# TOP.net
KiCad netlist of a schematic drawn in Altium Designer
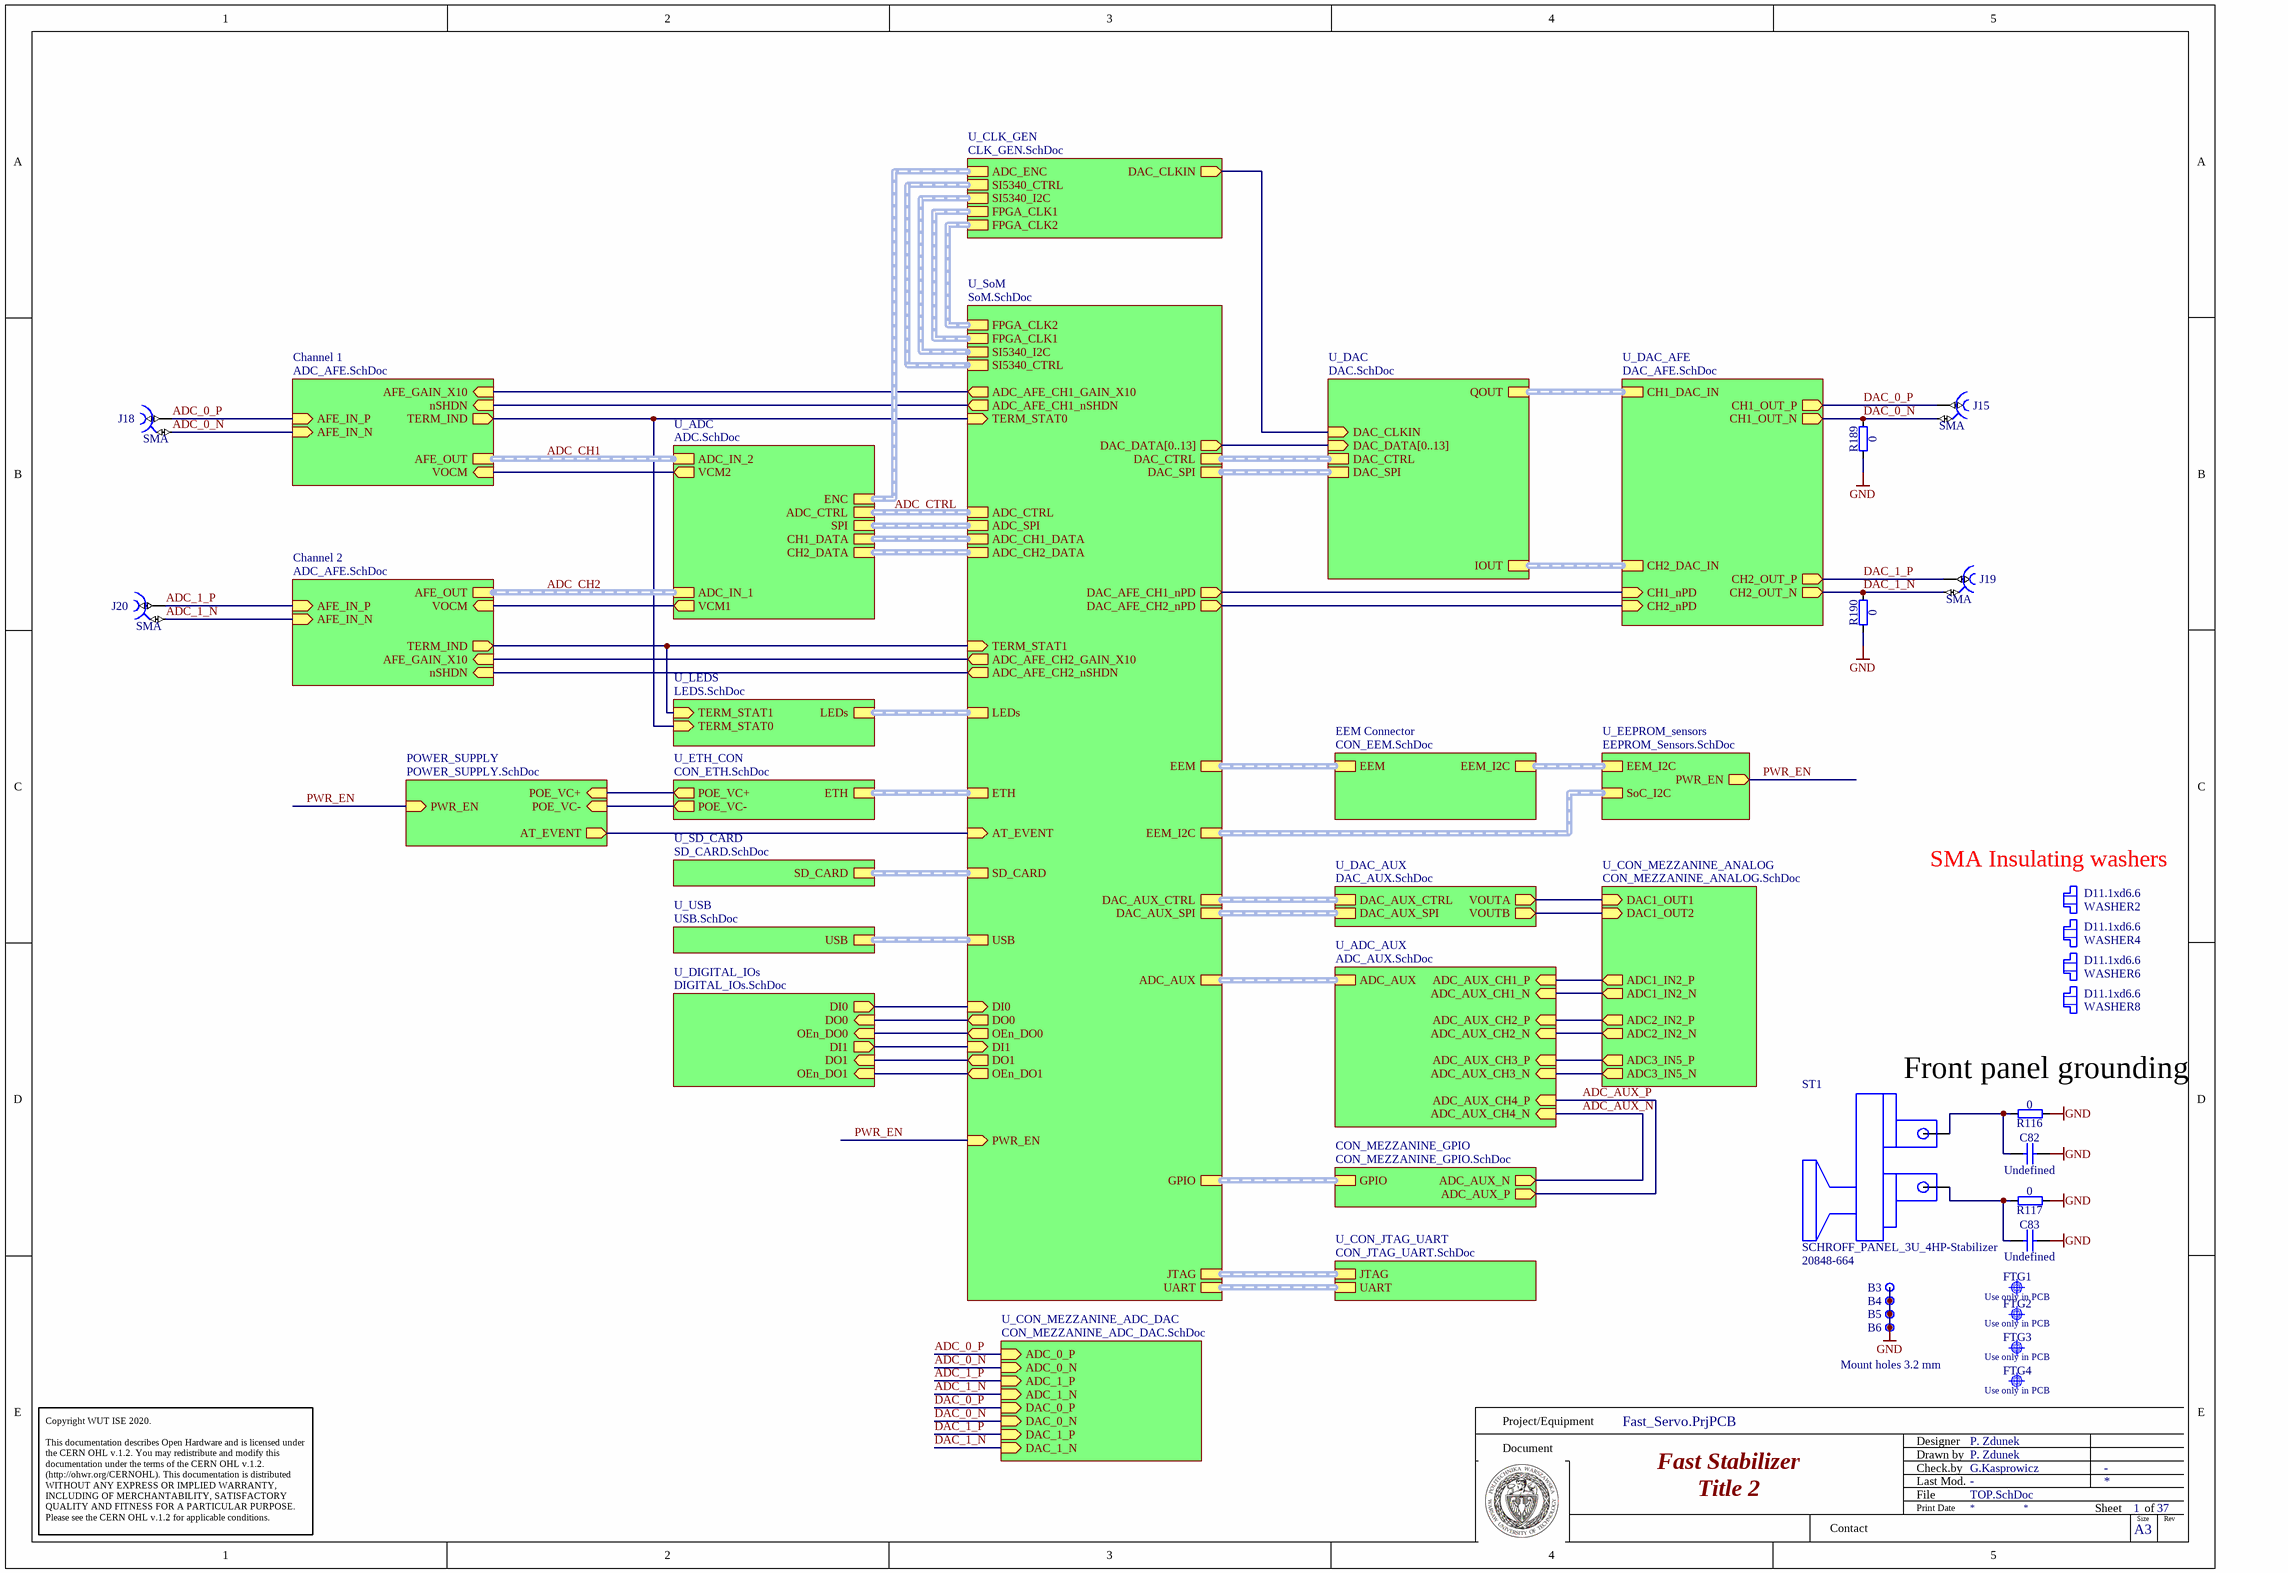
[diagram p0: TOP.SchDoc]

(export (version "E")
  (design (tool "Eeschema 10.0.6"))
  (components
    (comp (ref "B3")
      (value "Plated Hole")
      (footprint "MTG320_550")
      (description "Single Terminal Socket")
      (fields (field (name "PART NUMBER") "PLATED_HOLE3.2_PAD5.5") (field (name "AUTHOR") "CERN DEM JMW"))
      (libsource (lib "Eletro-mechanical") (part "Single Terminal Socket"))
    )
    (comp (ref "B4")
      (value "Plated Hole")
      (footprint "MTG320_550")
      (description "Single Terminal Socket")
      (fields (field (name "PART NUMBER") "PLATED_HOLE3.2_PAD5.5") (field (name "AUTHOR") "CERN DEM JMW"))
      (libsource (lib "Eletro-mechanical") (part "Single Terminal Socket"))
    )
    (comp (ref "B5")
      (value "Plated Hole")
      (footprint "MTG320_550")
      (description "Single Terminal Socket")
      (fields (field (name "PART NUMBER") "PLATED_HOLE3.2_PAD5.5") (field (name "AUTHOR") "CERN DEM JMW"))
      (libsource (lib "Eletro-mechanical") (part "Single Terminal Socket"))
    )
    (comp (ref "B6")
      (value "Plated Hole")
      (footprint "MTG320_550")
      (description "Single Terminal Socket")
      (fields (field (name "PART NUMBER") "PLATED_HOLE3.2_PAD5.5") (field (name "AUTHOR") "CERN DEM JMW"))
      (libsource (lib "Eletro-mechanical") (part "Single Terminal Socket"))
    )
    (comp (ref "C82")
      (value "Undefined")
      (footprint "CAPC1608X90N")
      (description "Non-polarised capacitor")
      (fields (field (name "PART NUMBER") "CC0603_NO-VALUE") (field (name "AUTHOR") "CERN DEM MR"))
      (libsource (lib "Capacitors") (part "Capacitor - non polarized"))
    )
    (comp (ref "C83")
      (value "Undefined")
      (footprint "CAPC1608X90N")
      (description "Non-polarised capacitor")
      (fields (field (name "PART NUMBER") "CC0603_NO-VALUE") (field (name "AUTHOR") "CERN DEM MR"))
      (libsource (lib "Capacitors") (part "Capacitor - non polarized"))
    )
    (comp (ref "FTG1")
      (value "Use only in PCB")
      (footprint "FIDUCIAL_TOP_C100-200")
      (description "Fiducial Target")
      (fields (field (name "PART NUMBER") "FIDUCIAL_TARGET_C100-200") (field (name "AUTHOR") "CERN DEM JLC"))
      (libsource (lib "Eletro-mechanical") (part "Fiducial Target"))
    )
    (comp (ref "FTG2")
      (value "Use only in PCB")
      (footprint "FIDUCIAL_TOP_S100-200")
      (description "Fiducial Target")
      (fields (field (name "PART NUMBER") "FIDUCIAL_TARGET_S100-200") (field (name "AUTHOR") "CERN DEM JLC"))
      (libsource (lib "Eletro-mechanical") (part "Fiducial Target"))
    )
    (comp (ref "FTG3")
      (value "Use only in PCB")
      (footprint "FIDUCIAL_TOP_S100-200")
      (description "Fiducial Target")
      (fields (field (name "PART NUMBER") "FIDUCIAL_TARGET_S100-200") (field (name "AUTHOR") "CERN DEM JLC"))
      (libsource (lib "Eletro-mechanical") (part "Fiducial Target"))
    )
    (comp (ref "FTG4")
      (value "Use only in PCB")
      (footprint "FIDUCIAL_TOP_S100-200")
      (description "Fiducial Target")
      (fields (field (name "PART NUMBER") "FIDUCIAL_TARGET_S100-200") (field (name "AUTHOR") "CERN DEM JLC"))
      (libsource (lib "Eletro-mechanical") (part "Fiducial Target"))
    )
    (comp (ref "J15")
      (value "SMA")
      (footprint "DELOCK_65848")
      (description "50 Ohm Through Hole SMA Right Angle PCB Jack")
      (fields
        (field (name "PART NUMBER") "DELOCK_65848")
        (field (name "MANUFACTURER") "DELOCK")
        (field (name "AUTHOR") "GK")
      )
      (libsource (lib "") (part "CON_SMA_DELOCK_65848_1"))
    )
    (comp (ref "J18")
      (value "SMA")
      (footprint "DELOCK_65848")
      (description "50 Ohm Through Hole SMA Right Angle PCB Jack")
      (fields
        (field (name "PART NUMBER") "DELOCK_65848")
        (field (name "MANUFACTURER") "DELOCK")
        (field (name "AUTHOR") "GK")
      )
      (libsource (lib "Connectors") (part "CON_SMA_DELOCK_65848"))
    )
    (comp (ref "J19")
      (value "SMA")
      (footprint "DELOCK_65848")
      (description "50 Ohm Through Hole SMA Right Angle PCB Jack")
      (fields
        (field (name "PART NUMBER") "DELOCK_65848")
        (field (name "MANUFACTURER") "DELOCK")
        (field (name "AUTHOR") "GK")
      )
      (libsource (lib "") (part "CON_SMA_DELOCK_65848_1"))
    )
    (comp (ref "J20")
      (value "SMA")
      (footprint "DELOCK_65848")
      (description "50 Ohm Through Hole SMA Right Angle PCB Jack")
      (fields
        (field (name "PART NUMBER") "DELOCK_65848")
        (field (name "MANUFACTURER") "DELOCK")
        (field (name "AUTHOR") "GK")
      )
      (libsource (lib "Connectors") (part "CON_SMA_DELOCK_65848"))
    )
    (comp (ref "R116")
      (value "0")
      (footprint "RESC1005X40N")
      (description "Resistor")
      (fields
        (field (name "PART NUMBER") "R0402_0R_JUMPER")
        (field (name "MANUFACTURER") "GENERIC")
        (field (name "AUTHOR") "CERN DEM JLC")
      )
      (libsource (lib "Resistors") (part "Resistor"))
    )
    (comp (ref "R117")
      (value "0")
      (footprint "RESC1005X40N")
      (description "Resistor")
      (fields
        (field (name "PART NUMBER") "R0402_0R_JUMPER")
        (field (name "MANUFACTURER") "GENERIC")
        (field (name "AUTHOR") "CERN DEM JLC")
      )
      (libsource (lib "Resistors") (part "Resistor"))
    )
    (comp (ref "R189")
      (value "0")
      (footprint "RESC1005X40N")
      (description "Resistor")
      (fields
        (field (name "PART NUMBER") "R0402_0R_JUMPER")
        (field (name "MANUFACTURER") "GENERIC")
        (field (name "AUTHOR") "CERN DEM JLC")
      )
      (libsource (lib "Resistors") (part "Resistor"))
    )
    (comp (ref "R190")
      (value "0")
      (footprint "RESC1005X40N")
      (description "Resistor")
      (fields
        (field (name "PART NUMBER") "R0402_0R_JUMPER")
        (field (name "MANUFACTURER") "GENERIC")
        (field (name "AUTHOR") "CERN DEM JLC")
      )
      (libsource (lib "Resistors") (part "Resistor"))
    )
    (comp (ref "ST1")
      (value "SCHROFF_PANEL_3U_4HP-Stabilizer")
      (footprint "SCHROFF_PANEL_3HP_4U - Stabilizer")
      (description "Schroff 3HP 4U EUROCARD Panel")
      (fields
        (field (name "MANUFACTURER") "Schroff")
        (field (name "MANUFACTURER PART NUMBER") "20818-017")
        (field (name "MANUFACTURER PART NUMBER 2") "20848-664")
      )
      (libsource (lib "Stabilizer") (part "SCHROFF_PANEL_3U_4HP_Stabilizer"))
    )
    (comp (ref "WASHER2")
      (value "D11.1xd6.6")
      (footprint "Keystone_7687")
      (description "SMA_Shoulder Washer")
      (fields (field (name "PART NUMBER") "Custom 3D printed") (field (name "AUTHOR") "GK"))
      (libsource (lib "Stabilizer") (part "Keystone_7687"))
    )
    (comp (ref "WASHER4")
      (value "D11.1xd6.6")
      (footprint "Keystone_7687")
      (description "SMA_Shoulder Washer")
      (fields (field (name "PART NUMBER") "Custom 3D printed") (field (name "AUTHOR") "GK"))
      (libsource (lib "Stabilizer") (part "Keystone_7687"))
    )
    (comp (ref "WASHER6")
      (value "D11.1xd6.6")
      (footprint "Keystone_7687")
      (description "SMA_Shoulder Washer")
      (fields (field (name "PART NUMBER") "Custom 3D printed") (field (name "AUTHOR") "GK"))
      (libsource (lib "Stabilizer") (part "Keystone_7687"))
    )
    (comp (ref "WASHER8")
      (value "D11.1xd6.6")
      (footprint "Keystone_7687")
      (description "SMA_Shoulder Washer")
      (fields (field (name "PART NUMBER") "Custom 3D printed") (field (name "AUTHOR") "GK"))
      (libsource (lib "Stabilizer") (part "Keystone_7687"))
    )
  )
  (nets
    (net (code "10") (name "/ADC_0_N") (class "Default")
      (node (ref "J18") (pin "2") (pinfunction "2_2") (pintype "bidirectional"))
    )
    (net (code "11") (name "/ADC_0_P") (class "Default")
      (node (ref "J18") (pin "1") (pinfunction "1_1") (pintype "bidirectional"))
    )
    (net (code "12") (name "/ADC_1_N") (class "Default")
      (node (ref "J20") (pin "2") (pinfunction "2_2") (pintype "bidirectional"))
    )
    (net (code "13") (name "/ADC_1_P") (class "Default")
      (node (ref "J20") (pin "1") (pinfunction "1_1") (pintype "bidirectional"))
    )
    (net (code "28") (name "/DAC_0_N") (class "Default")
      (node (ref "J15") (pin "2") (pinfunction "2_2") (pintype "bidirectional"))
      (node (ref "R189") (pin "2") (pinfunction "2_2") (pintype "passive"))
    )
    (net (code "29") (name "/DAC_0_P") (class "Default")
      (node (ref "J15") (pin "1") (pinfunction "1_1") (pintype "bidirectional"))
    )
    (net (code "30") (name "/DAC_1_N") (class "Default")
      (node (ref "J19") (pin "2") (pinfunction "2_2") (pintype "bidirectional"))
      (node (ref "R190") (pin "2") (pinfunction "2_2") (pintype "passive"))
    )
    (net (code "31") (name "/DAC_1_P") (class "Default")
      (node (ref "J19") (pin "1") (pinfunction "1_1") (pintype "bidirectional"))
    )
    (net (code "72") (name "GND") (class "Default")
      (node (ref "B3") (pin "1") (pinfunction "1_1") (pintype "bidirectional"))
      (node (ref "B4") (pin "1") (pinfunction "1_1") (pintype "bidirectional"))
      (node (ref "B5") (pin "1") (pinfunction "1_1") (pintype "bidirectional"))
      (node (ref "B6") (pin "1") (pinfunction "1_1") (pintype "bidirectional"))
      (node (ref "C82") (pin "2") (pinfunction "2_2") (pintype "passive"))
      (node (ref "C83") (pin "2") (pinfunction "2_2") (pintype "passive"))
      (node (ref "R116") (pin "1") (pinfunction "1_1") (pintype "passive"))
      (node (ref "R117") (pin "1") (pinfunction "1_1") (pintype "passive"))
      (node (ref "R189") (pin "1") (pinfunction "1_1") (pintype "passive"))
      (node (ref "R190") (pin "1") (pinfunction "1_1") (pintype "passive"))
    )
    (net (code "73") (name "Net-(C82-Pad1)") (class "Default")
      (node (ref "C82") (pin "1") (pinfunction "1_1") (pintype "passive"))
      (node (ref "R116") (pin "2") (pinfunction "2_2") (pintype "passive"))
      (node (ref "ST1") (pin "1") (pinfunction "1_1") (pintype "passive"))
    )
    (net (code "74") (name "Net-(C83-Pad1)") (class "Default")
      (node (ref "C83") (pin "1") (pinfunction "1_1") (pintype "passive"))
      (node (ref "R117") (pin "2") (pinfunction "2_2") (pintype "passive"))
      (node (ref "ST1") (pin "0") (pinfunction "0_0") (pintype "passive"))
    )
  )
)
